# razbot.net
KiCad netlist of a schematic drawn in Altium Designer
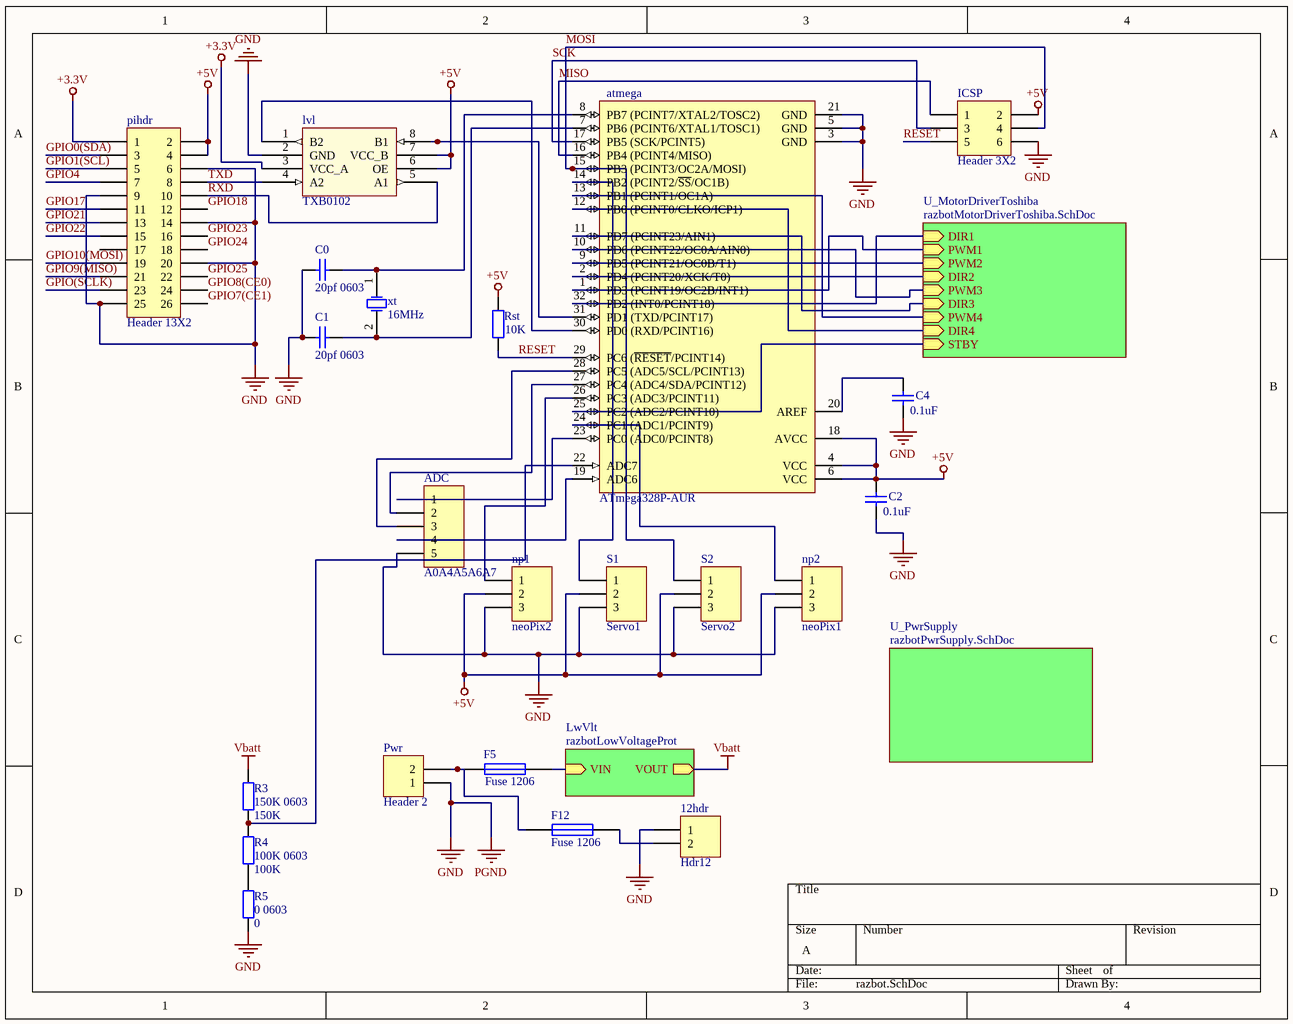
[diagram p0: razbot.SchDoc]

(export (version "E")
  (design (tool "Eeschema 10.0.6"))
  (components
    (comp (ref "12hdr")
      (value "Hdr12")
      (footprint "PiBotPcbLib1:PwrPlug1")
      (description "Header, 2-Pin")
      (fields (field (name "PUBLISHER") "Altium Limited"))
      (libsource (lib "") (part "Header 2_1"))
    )
    (comp (ref "ADC")
      (value "A0A4A5A6A7")
      (footprint "HDR1X5")
      (description "Header, 5-Pin")
      (fields (field (name "PUBLISHER") "Altium Limited"))
      (libsource (lib "Miscellaneous Connectors") (part "Header 5"))
    )
    (comp (ref "atmega")
      (value "ATmega328P-AUR")
      (footprint "Altera Footprints:TQFP32_N")
      (fields (field (name "PUBLISHER") "Altium Limited"))
      (libsource (lib "Atmel Microcontroller 8-Bit megaAVR") (part "ATmega328P-AUR"))
    )
    (comp (ref "C0")
      (value "20pf 0603")
      (footprint "Miscellaneous Devices:J1-0603")
      (description "Capacitor")
      (fields (field (name "PUBLISHER") "Altium Limited"))
      (libsource (lib "Miscellaneous Devices") (part "Cap"))
    )
    (comp (ref "C1")
      (value "20pf 0603")
      (footprint "Miscellaneous Devices:J1-0603")
      (description "Capacitor")
      (fields (field (name "PUBLISHER") "Altium Limited"))
      (libsource (lib "Miscellaneous Devices") (part "Cap"))
    )
    (comp (ref "C2")
      (value "0.1uF")
      (footprint "Miscellaneous Devices:J1-0603")
      (description "Capacitor")
      (fields (field (name "Comment") "0.1uF 0603") (field (name "PUBLISHER") "Altium Limited"))
      (libsource (lib "Miscellaneous Devices") (part "Cap"))
    )
    (comp (ref "C4")
      (value "0.1uF")
      (footprint "J1-0603")
      (description "Capacitor")
      (fields (field (name "Comment") "0.1uF 0603") (field (name "PUBLISHER") "Altium Limited"))
      (libsource (lib "Miscellaneous Devices") (part "Cap"))
    )
    (comp (ref "F5")
      (value "Fuse 1206")
      (footprint "Miscellaneous Devices:3216[1206]")
      (description "Fuse")
      (fields (field (name "PUBLISHER") "Altium Limited"))
      (libsource (lib "Miscellaneous Devices") (part "Fuse 1"))
    )
    (comp (ref "F12")
      (value "Fuse 1206")
      (footprint "Miscellaneous Devices:3216[1206]")
      (description "Fuse 12V 5A")
      (fields (field (name "PUBLISHER") "Altium Limited"))
      (libsource (lib "Miscellaneous Devices") (part "Fuse 1"))
    )
    (comp (ref "ICSP")
      (value "Header 3X2")
      (footprint "HDR2X3")
      (description "Header, 3-Pin, Dual row")
      (fields (field (name "PUBLISHER") "Altium Limited"))
      (libsource (lib "Miscellaneous Connectors") (part "Header 3X2"))
    )
    (comp (ref "lvl")
      (value "TXB0102")
      (footprint "PiBotPcbLib1:TSSOP50P310X90-8N")
      (description "3.3V Level translator")
      (libsource (lib "RpiPaw1_SchLib") (part "TXB0102"))
    )
    (comp (ref "np1")
      (value "neoPix2")
      (footprint "HDR1X3")
      (description "Header, 3-Pin")
      (fields (field (name "PUBLISHER") "Altium Limited"))
      (libsource (lib "Miscellaneous Connectors") (part "Header 3"))
    )
    (comp (ref "np2")
      (value "neoPix1")
      (footprint "HDR1X3")
      (description "Header, 3-Pin")
      (fields (field (name "PUBLISHER") "Altium Limited"))
      (libsource (lib "Miscellaneous Connectors") (part "Header 3"))
    )
    (comp (ref "pihdr")
      (value "Header 13X2")
      (footprint "HDR2X13")
      (description "Header, 13-Pin, Dual row")
      (fields (field (name "PUBLISHER") "Altium Limited"))
      (libsource (lib "Miscellaneous Connectors") (part "Header 13X2"))
    )
    (comp (ref "Pwr")
      (value "Header 2")
      (footprint "PiBotPcbLib1:PwrPlug1")
      (description "Header, 2-Pin")
      (fields (field (name "PUBLISHER") "Altium Limited"))
      (libsource (lib "Miscellaneous Connectors") (part "Header 2"))
    )
    (comp (ref "R3")
      (value "150K 0603")
      (footprint "J1-0603")
      (description "Resistor")
      (fields (field (name "ALTIUM_VALUE") "150K") (field (name "PUBLISHER") "Altium Limited"))
      (libsource (lib "Miscellaneous Devices") (part "Res2"))
    )
    (comp (ref "R4")
      (value "100K 0603")
      (footprint "J1-0603")
      (description "Resistor")
      (fields (field (name "ALTIUM_VALUE") "100K") (field (name "PUBLISHER") "Altium Limited"))
      (libsource (lib "Miscellaneous Devices") (part "Res2"))
    )
    (comp (ref "R5")
      (value "0 0603")
      (footprint "J1-0603")
      (description "Resistor")
      (fields (field (name "ALTIUM_VALUE") "0") (field (name "PUBLISHER") "Altium Limited"))
      (libsource (lib "Miscellaneous Devices") (part "Res2"))
    )
    (comp (ref "Rst")
      (value "10K")
      (footprint "J1-0603")
      (description "Resistor")
      (fields (field (name "Comment") "10K 0603") (field (name "PUBLISHER") "Altium Limited"))
      (libsource (lib "Miscellaneous Devices") (part "Res2"))
    )
    (comp (ref "S1")
      (value "Servo1")
      (footprint "HDR1X3")
      (description "Header, 3-Pin")
      (fields (field (name "PUBLISHER") "Altium Limited"))
      (libsource (lib "Miscellaneous Connectors") (part "Header 3"))
    )
    (comp (ref "S2")
      (value "Servo2")
      (footprint "HDR1X3")
      (description "Header, 3-Pin")
      (fields (field (name "PUBLISHER") "Altium Limited"))
      (libsource (lib "Miscellaneous Connectors") (part "Header 3"))
    )
    (comp (ref "xt")
      (value "16MHz")
      (footprint "Axial 0.2")
      (description "Crystal Oscillator")
      (fields (field (name "PUBLISHER") "Altium Limited"))
      (libsource (lib "Miscellaneous Devices") (part "XTAL"))
    )
  )
  (nets
    (net (code "1") (name "+3.3V") (class "Default")
      (node (ref "lvl") (pin "3") (pinfunction "VCC_A_3") (pintype "power_in"))
      (node (ref "pihdr") (pin "1") (pinfunction "1_1") (pintype "passive"))
    )
    (net (code "2") (name "+5V") (class "Default")
      (node (ref "C2") (pin "2") (pinfunction "2_2") (pintype "passive"))
      (node (ref "ICSP") (pin "2") (pinfunction "2_2") (pintype "passive"))
      (node (ref "Rst") (pin "2") (pinfunction "2_2") (pintype "passive"))
      (node (ref "S1") (pin "2") (pinfunction "2_2") (pintype "passive"))
      (node (ref "S2") (pin "2") (pinfunction "2_2") (pintype "passive"))
      (node (ref "atmega") (pin "18") (pinfunction "AVCC_18") (pintype "power_in"))
      (node (ref "atmega") (pin "4") (pinfunction "VCC_4") (pintype "power_in"))
      (node (ref "atmega") (pin "6") (pinfunction "VCC_6") (pintype "power_in"))
      (node (ref "lvl") (pin "6") (pinfunction "OE_6") (pintype "passive"))
      (node (ref "lvl") (pin "7") (pinfunction "VCC_B_7") (pintype "power_in"))
      (node (ref "np1") (pin "2") (pinfunction "2_2") (pintype "passive"))
      (node (ref "np2") (pin "2") (pinfunction "2_2") (pintype "passive"))
      (node (ref "pihdr") (pin "2") (pinfunction "2_2") (pintype "passive"))
      (node (ref "pihdr") (pin "4") (pinfunction "4_4") (pintype "passive"))
    )
    (net (code "3") (name "/DIR1") (class "Default")
      (node (ref "atmega") (pin "32") (pinfunction "PD2_(INT0/PCINT18)_32") (pintype "bidirectional"))
    )
    (net (code "4") (name "/DIR2") (class "Default")
      (node (ref "atmega") (pin "2") (pinfunction "PD4_(PCINT20/XCK/T0)_2") (pintype "bidirectional"))
    )
    (net (code "5") (name "/DIR3") (class "Default")
      (node (ref "atmega") (pin "11") (pinfunction "PD7_(PCINT23/AIN1)_11") (pintype "bidirectional"))
    )
    (net (code "6") (name "/DIR4") (class "Default")
      (node (ref "atmega") (pin "12") (pinfunction "PB0_(PCINT0/CLKO/ICP1)_12") (pintype "bidirectional"))
    )
    (net (code "7") (name "/GPIO(SCLK)") (class "Default")
      (node (ref "pihdr") (pin "23") (pinfunction "23_23") (pintype "passive"))
    )
    (net (code "8") (name "/GPIO0(SDA)") (class "Default")
      (node (ref "pihdr") (pin "3") (pinfunction "3_3") (pintype "passive"))
    )
    (net (code "9") (name "/GPIO1(SCL)") (class "Default")
      (node (ref "pihdr") (pin "5") (pinfunction "5_5") (pintype "passive"))
    )
    (net (code "10") (name "/GPIO4") (class "Default")
      (node (ref "pihdr") (pin "7") (pinfunction "7_7") (pintype "passive"))
    )
    (net (code "11") (name "/GPIO7(CE1)") (class "Default")
      (node (ref "pihdr") (pin "26") (pinfunction "26_26") (pintype "passive"))
    )
    (net (code "12") (name "/GPIO8(CE0)") (class "Default")
      (node (ref "pihdr") (pin "24") (pinfunction "24_24") (pintype "passive"))
    )
    (net (code "13") (name "/GPIO9(MISO)") (class "Default")
      (node (ref "pihdr") (pin "21") (pinfunction "21_21") (pintype "passive"))
    )
    (net (code "14") (name "/GPIO10(MOSI)") (class "Default")
      (node (ref "pihdr") (pin "19") (pinfunction "19_19") (pintype "passive"))
    )
    (net (code "15") (name "/GPIO17") (class "Default")
      (node (ref "pihdr") (pin "11") (pinfunction "11_11") (pintype "passive"))
    )
    (net (code "16") (name "/GPIO18") (class "Default")
      (node (ref "pihdr") (pin "12") (pinfunction "12_12") (pintype "passive"))
    )
    (net (code "17") (name "/GPIO21") (class "Default")
      (node (ref "pihdr") (pin "13") (pinfunction "13_13") (pintype "passive"))
    )
    (net (code "18") (name "/GPIO22") (class "Default")
      (node (ref "pihdr") (pin "15") (pinfunction "15_15") (pintype "passive"))
    )
    (net (code "19") (name "/GPIO23") (class "Default")
      (node (ref "pihdr") (pin "16") (pinfunction "16_16") (pintype "passive"))
    )
    (net (code "20") (name "/GPIO24") (class "Default")
      (node (ref "pihdr") (pin "18") (pinfunction "18_18") (pintype "passive"))
    )
    (net (code "21") (name "/GPIO25") (class "Default")
      (node (ref "pihdr") (pin "22") (pinfunction "22_22") (pintype "passive"))
    )
    (net (code "22") (name "/MISO") (class "Default")
      (node (ref "ICSP") (pin "1") (pinfunction "1_1") (pintype "passive"))
      (node (ref "atmega") (pin "16") (pinfunction "PB4_(PCINT4/MISO)_16") (pintype "bidirectional"))
    )
    (net (code "23") (name "/MOSI") (class "Default")
      (node (ref "ICSP") (pin "4") (pinfunction "4_4") (pintype "passive"))
      (node (ref "S2") (pin "1") (pinfunction "1_1") (pintype "passive"))
      (node (ref "atmega") (pin "15") (pinfunction "PB3_(PCINT3/OC2A/MOSI)_15") (pintype "bidirectional"))
    )
    (net (code "24") (name "/PWM1") (class "Default")
      (node (ref "atmega") (pin "1") (pinfunction "PD3_(PCINT19/OC2B/INT1)_1") (pintype "bidirectional"))
    )
    (net (code "25") (name "/PWM2") (class "Default")
      (node (ref "atmega") (pin "9") (pinfunction "PD5_(PCINT21/OC0B/T1)_9") (pintype "bidirectional"))
    )
    (net (code "26") (name "/PWM3") (class "Default")
      (node (ref "atmega") (pin "10") (pinfunction "PD6_(PCINT22/OC0A/AIN0)_10") (pintype "bidirectional"))
    )
    (net (code "27") (name "/PWM4") (class "Default")
      (node (ref "atmega") (pin "13") (pinfunction "PB1_(PCINT1/OC1A)_13") (pintype "bidirectional"))
    )
    (net (code "28") (name "/RESET") (class "Default")
      (node (ref "ICSP") (pin "5") (pinfunction "5_5") (pintype "passive"))
      (node (ref "Rst") (pin "1") (pinfunction "1_1") (pintype "passive"))
      (node (ref "atmega") (pin "29") (pinfunction "PC6_(~{RESET}/PCINT14)_29") (pintype "bidirectional"))
    )
    (net (code "29") (name "/RXD") (class "Default")
      (node (ref "lvl") (pin "5") (pinfunction "A1_5") (pintype "output"))
      (node (ref "pihdr") (pin "10") (pinfunction "10_10") (pintype "passive"))
    )
    (net (code "30") (name "/SCK") (class "Default")
      (node (ref "ICSP") (pin "3") (pinfunction "3_3") (pintype "passive"))
      (node (ref "atmega") (pin "17") (pinfunction "PB5_(SCK/PCINT5)_17") (pintype "bidirectional"))
    )
    (net (code "31") (name "/STBY") (class "Default")
      (node (ref "atmega") (pin "25") (pinfunction "PC2_(ADC2/PCINT10)_25") (pintype "bidirectional"))
    )
    (net (code "32") (name "/TXD") (class "Default")
      (node (ref "lvl") (pin "4") (pinfunction "A2_4") (pintype "input"))
      (node (ref "pihdr") (pin "8") (pinfunction "8_8") (pintype "passive"))
    )
    (net (code "33") (name "/VIN") (class "Default")
      (node (ref "F5") (pin "2") (pinfunction "2_2") (pintype "passive"))
    )
    (net (code "34") (name "GND") (class "Default")
      (node (ref "12hdr") (pin "1") (pinfunction "1_1") (pintype "passive"))
      (node (ref "ADC") (pin "5") (pinfunction "5_5") (pintype "passive"))
      (node (ref "C0") (pin "1") (pinfunction "1_1") (pintype "passive"))
      (node (ref "C1") (pin "1") (pinfunction "1_1") (pintype "passive"))
      (node (ref "C2") (pin "1") (pinfunction "1_1") (pintype "passive"))
      (node (ref "C4") (pin "1") (pinfunction "1_1") (pintype "passive"))
      (node (ref "ICSP") (pin "6") (pinfunction "6_6") (pintype "passive"))
      (node (ref "Pwr") (pin "1") (pinfunction "1_1") (pintype "passive"))
      (node (ref "R5") (pin "1") (pinfunction "1_1") (pintype "passive"))
      (node (ref "S1") (pin "3") (pinfunction "3_3") (pintype "passive"))
      (node (ref "S2") (pin "3") (pinfunction "3_3") (pintype "passive"))
      (node (ref "atmega") (pin "21") (pinfunction "GND_21") (pintype "power_in"))
      (node (ref "atmega") (pin "3") (pinfunction "GND_3") (pintype "power_in"))
      (node (ref "atmega") (pin "5") (pinfunction "GND_5") (pintype "power_in"))
      (node (ref "lvl") (pin "2") (pinfunction "GND_2") (pintype "power_in"))
      (node (ref "np1") (pin "3") (pinfunction "3_3") (pintype "passive"))
      (node (ref "np2") (pin "3") (pinfunction "3_3") (pintype "passive"))
      (node (ref "pihdr") (pin "14") (pinfunction "14_14") (pintype "passive"))
      (node (ref "pihdr") (pin "20") (pinfunction "20_20") (pintype "passive"))
      (node (ref "pihdr") (pin "25") (pinfunction "25_25") (pintype "passive"))
      (node (ref "pihdr") (pin "6") (pinfunction "6_6") (pintype "passive"))
      (node (ref "pihdr") (pin "9") (pinfunction "9_9") (pintype "passive"))
    )
    (net (code "35") (name "Net-(12hdr-Pad2)") (class "Default")
      (node (ref "12hdr") (pin "2") (pinfunction "2_2") (pintype "passive"))
      (node (ref "F12") (pin "2") (pinfunction "2_2") (pintype "passive"))
    )
    (net (code "36") (name "Net-(F12-Pad1)") (class "Default")
      (node (ref "F12") (pin "1") (pinfunction "1_1") (pintype "passive"))
      (node (ref "F5") (pin "1") (pinfunction "1_1") (pintype "passive"))
      (node (ref "Pwr") (pin "2") (pinfunction "2_2") (pintype "passive"))
    )
    (net (code "37") (name "Net-(R4-Pad1)") (class "Default")
      (node (ref "R4") (pin "1") (pinfunction "1_1") (pintype "passive"))
      (node (ref "R5") (pin "2") (pinfunction "2_2") (pintype "passive"))
    )
    (net (code "38") (name "Net-(atmega-ADC6)") (class "Default")
      (node (ref "ADC") (pin "4") (pinfunction "4_4") (pintype "passive"))
      (node (ref "atmega") (pin "19") (pinfunction "ADC6_19") (pintype "input"))
    )
    (net (code "39") (name "Net-(atmega-ADC7)") (class "Default")
      (node (ref "R3") (pin "1") (pinfunction "1_1") (pintype "passive"))
      (node (ref "R4") (pin "2") (pinfunction "2_2") (pintype "passive"))
      (node (ref "atmega") (pin "22") (pinfunction "ADC7_22") (pintype "input"))
    )
    (net (code "40") (name "Net-(atmega-AREF)") (class "Default")
      (node (ref "C4") (pin "2") (pinfunction "2_2") (pintype "passive"))
      (node (ref "atmega") (pin "20") (pinfunction "AREF_20") (pintype "passive"))
    )
    (net (code "41") (name "Net-(atmega-PB2_(PCINT2{slash}~{SS}{slash}OC1B))") (class "Default")
      (node (ref "S1") (pin "1") (pinfunction "1_1") (pintype "passive"))
      (node (ref "atmega") (pin "14") (pinfunction "PB2_(PCINT2/~{SS}/OC1B)_14") (pintype "bidirectional"))
    )
    (net (code "42") (name "Net-(atmega-PB6_(PCINT6{slash}XTAL1{slash}TOSC1))") (class "Default")
      (node (ref "C1") (pin "2") (pinfunction "2_2") (pintype "passive"))
      (node (ref "atmega") (pin "7") (pinfunction "PB6_(PCINT6/XTAL1/TOSC1)_7") (pintype "bidirectional"))
      (node (ref "xt") (pin "2") (pinfunction "OSC2_2") (pintype "passive"))
    )
    (net (code "43") (name "Net-(atmega-PB7_(PCINT7{slash}XTAL2{slash}TOSC2))") (class "Default")
      (node (ref "C0") (pin "2") (pinfunction "2_2") (pintype "passive"))
      (node (ref "atmega") (pin "8") (pinfunction "PB7_(PCINT7/XTAL2/TOSC2)_8") (pintype "bidirectional"))
      (node (ref "xt") (pin "1") (pinfunction "OSC1_1") (pintype "passive"))
    )
    (net (code "44") (name "Net-(atmega-PC0_(ADC0{slash}PCINT8))") (class "Default")
      (node (ref "ADC") (pin "1") (pinfunction "1_1") (pintype "passive"))
      (node (ref "atmega") (pin "23") (pinfunction "PC0_(ADC0/PCINT8)_23") (pintype "bidirectional"))
    )
    (net (code "45") (name "Net-(atmega-PC1_(ADC1{slash}PCINT9))") (class "Default")
      (node (ref "atmega") (pin "24") (pinfunction "PC1_(ADC1/PCINT9)_24") (pintype "bidirectional"))
      (node (ref "np2") (pin "1") (pinfunction "1_1") (pintype "passive"))
    )
    (net (code "46") (name "Net-(atmega-PC3_(ADC3{slash}PCINT11))") (class "Default")
      (node (ref "atmega") (pin "26") (pinfunction "PC3_(ADC3/PCINT11)_26") (pintype "bidirectional"))
      (node (ref "np1") (pin "1") (pinfunction "1_1") (pintype "passive"))
    )
    (net (code "47") (name "Net-(atmega-PC4_(ADC4{slash}SDA{slash}PCINT12))") (class "Default")
      (node (ref "ADC") (pin "2") (pinfunction "2_2") (pintype "passive"))
      (node (ref "atmega") (pin "27") (pinfunction "PC4_(ADC4/SDA/PCINT12)_27") (pintype "bidirectional"))
    )
    (net (code "48") (name "Net-(atmega-PC5_(ADC5{slash}SCL{slash}PCINT13))") (class "Default")
      (node (ref "ADC") (pin "3") (pinfunction "3_3") (pintype "passive"))
      (node (ref "atmega") (pin "28") (pinfunction "PC5_(ADC5/SCL/PCINT13)_28") (pintype "bidirectional"))
    )
    (net (code "49") (name "Net-(atmega-PD0_(RXD{slash}PCINT16))") (class "Default")
      (node (ref "atmega") (pin "30") (pinfunction "PD0_(RXD/PCINT16)_30") (pintype "bidirectional"))
      (node (ref "lvl") (pin "1") (pinfunction "B2_1") (pintype "output"))
    )
    (net (code "50") (name "Net-(atmega-PD1_(TXD{slash}PCINT17))") (class "Default")
      (node (ref "atmega") (pin "31") (pinfunction "PD1_(TXD/PCINT17)_31") (pintype "bidirectional"))
      (node (ref "lvl") (pin "8") (pinfunction "B1_8") (pintype "input"))
    )
    (net (code "51") (name "Vbatt") (class "Default")
      (node (ref "R3") (pin "2") (pinfunction "2_2") (pintype "passive"))
    )
    (net (code "52") (name "unconnected-(pihdr-Pad17)") (class "Default")
      (node (ref "pihdr") (pin "17") (pinfunction "17_17") (pintype "passive"))
    )
  )
)
